# Project.net
KiCad netlist of a schematic drawn in EasyEDA Pro
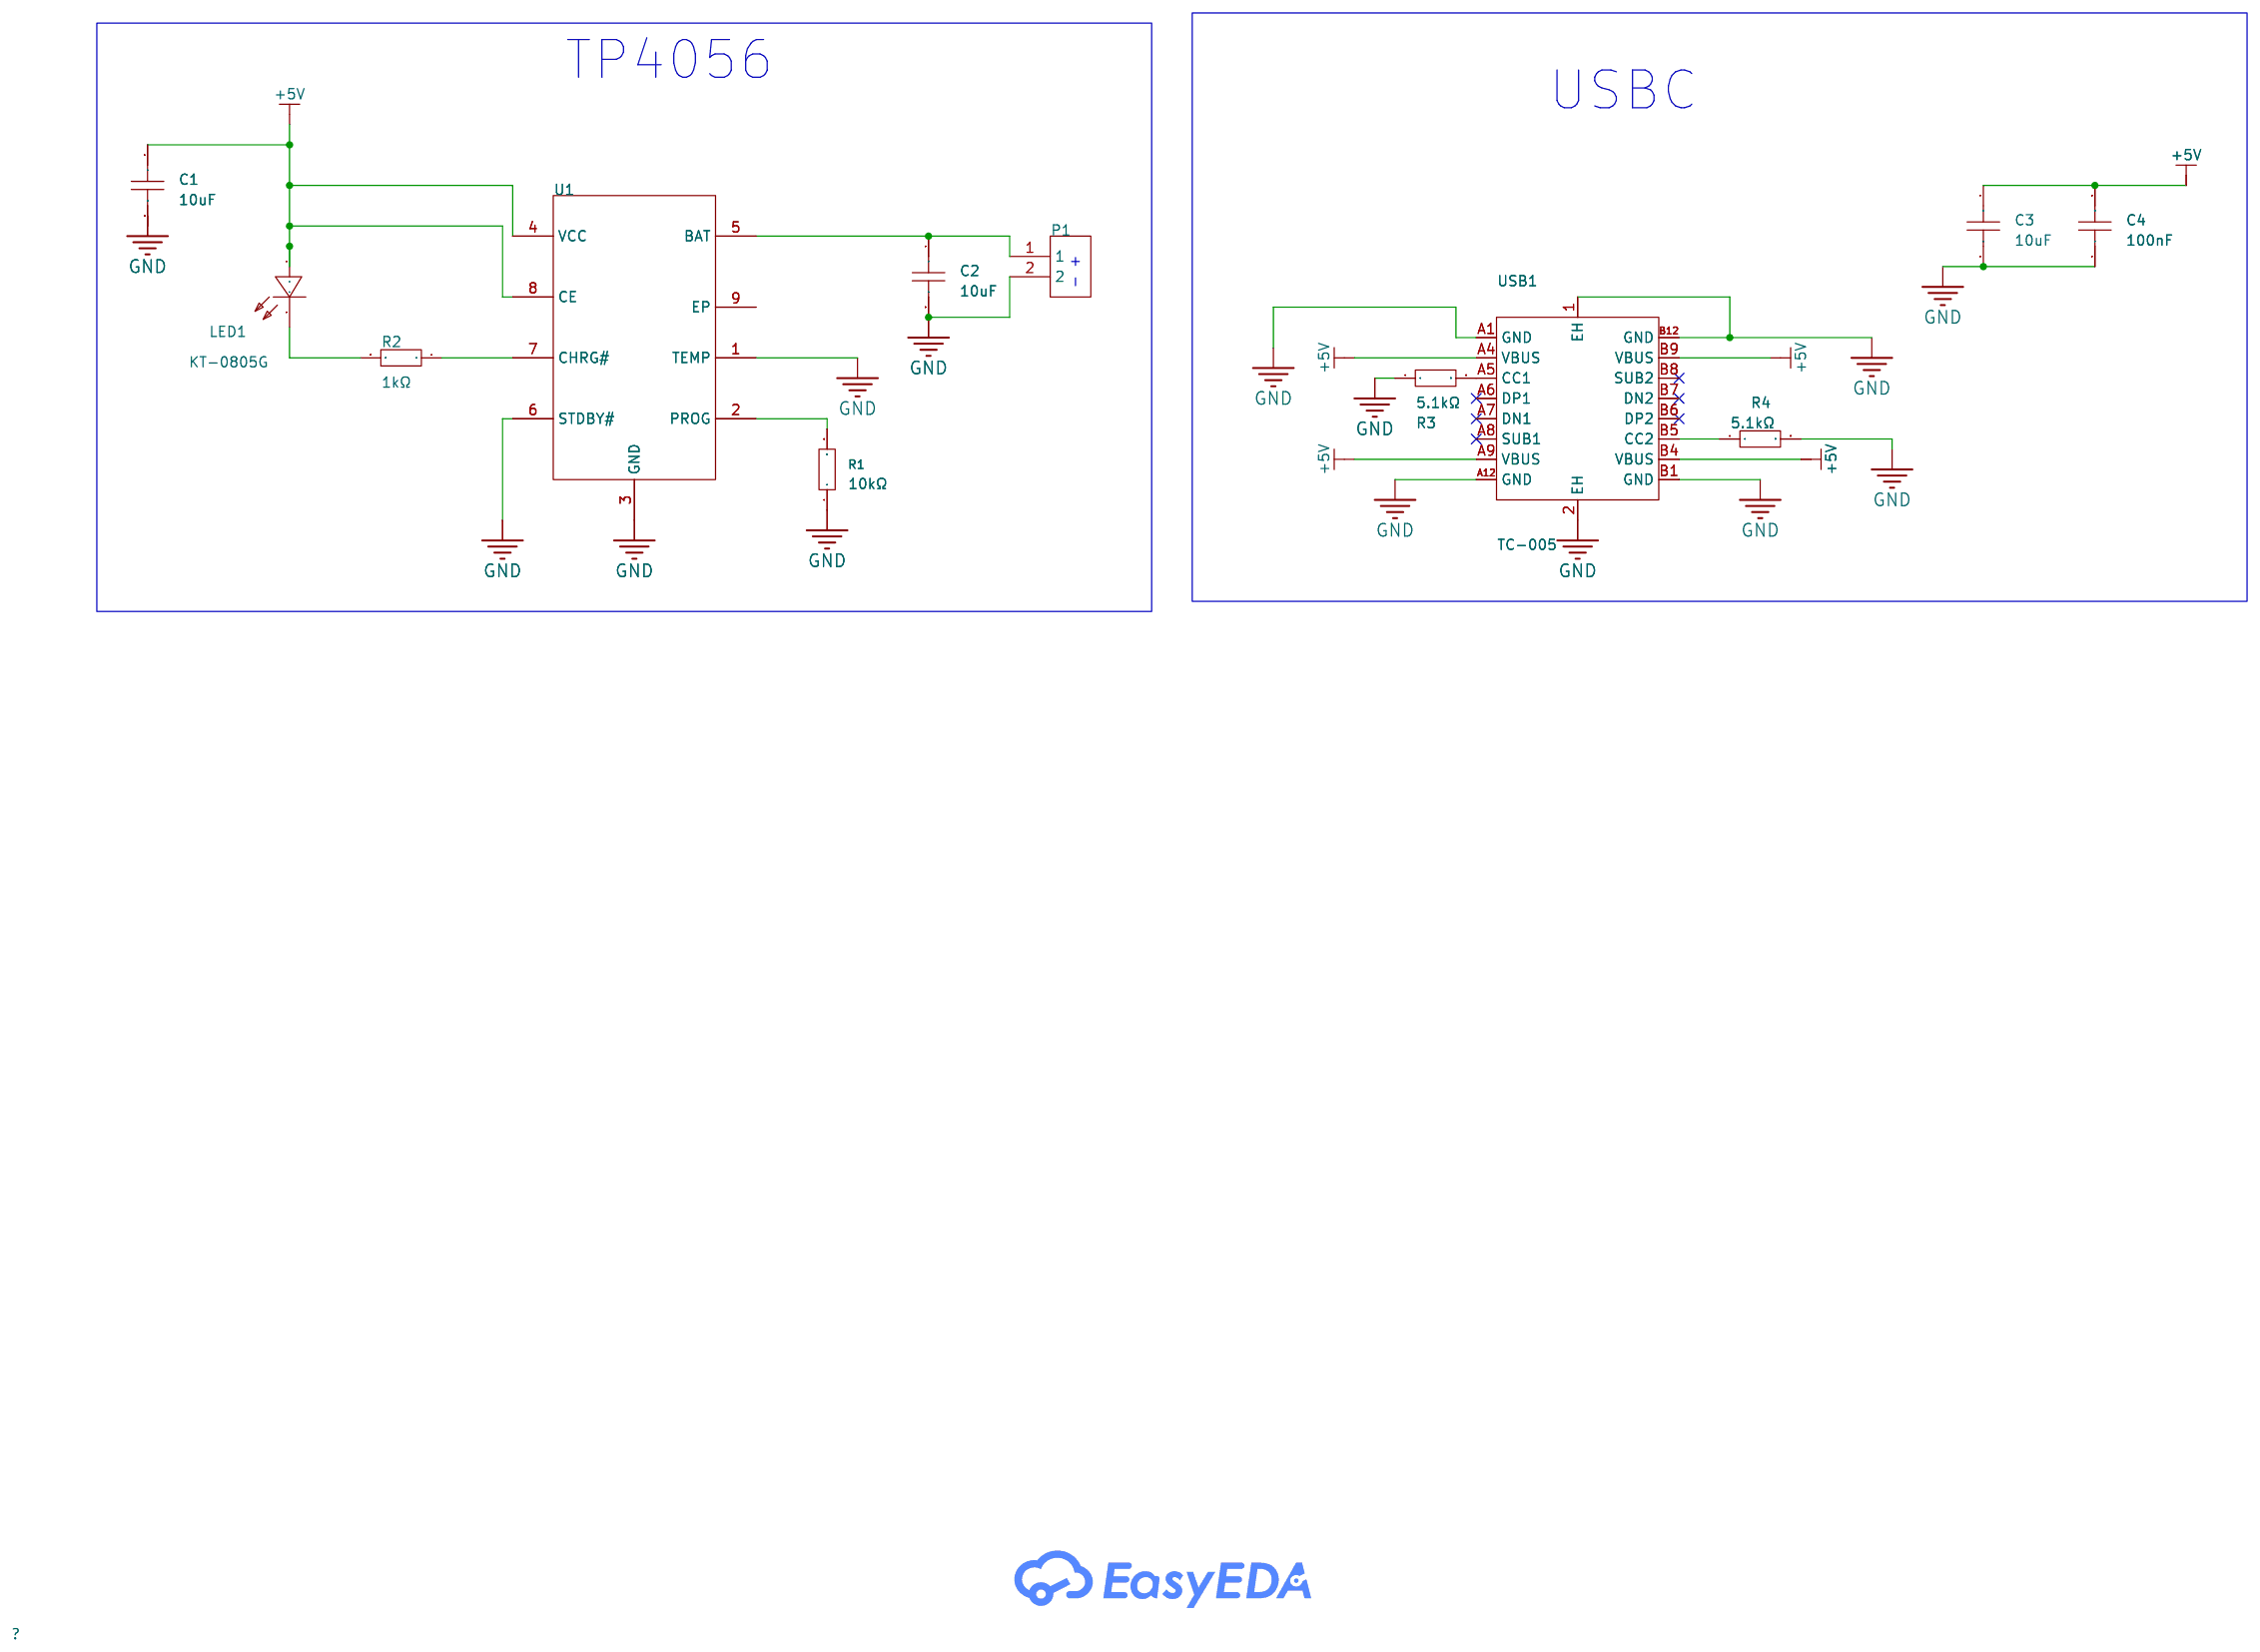
[diagram p0: schematic sheet]

(export (version "E")
  (design (tool "Eeschema 10.0.6"))
  (components
    (comp (ref "C1")
      (value "10uF")
      (footprint "easyedapro:C0805")
      (description "Capacitance:10uF Tolerance:±10% Tolerance:±10% Voltage Rating:25V Temperature Coefficient:X5R")
      (fields
        (field (name "Manufacturer Part") "CL21A106KAYNNNE")
        (field (name "Manufacturer") "SAMSUNG(三星)")
      )
      (libsource (lib "easyedapro") (part "CL21A106KAYNNNE"))
    )
    (comp (ref "C2")
      (value "10uF")
      (footprint "easyedapro:C0805")
      (description "Capacitance:10uF Tolerance:±10% Tolerance:±10% Voltage Rating:25V Temperature Coefficient:X5R")
      (fields
        (field (name "Manufacturer Part") "CL21A106KAYNNNE")
        (field (name "Manufacturer") "SAMSUNG(三星)")
      )
      (libsource (lib "easyedapro") (part "CL21A106KAYNNNE"))
    )
    (comp (ref "C3")
      (value "10uF")
      (footprint "easyedapro:C0805")
      (description "Capacitance:10uF Tolerance:±10% Tolerance:±10% Voltage Rating:25V Temperature Coefficient:X5R")
      (fields
        (field (name "Manufacturer Part") "CL21A106KAYNNNE")
        (field (name "Manufacturer") "SAMSUNG(三星)")
      )
      (libsource (lib "easyedapro") (part "CL21A106KAYNNNE"))
    )
    (comp (ref "C4")
      (value "100nF")
      (footprint "easyedapro:C0402")
      (description "Capacitance:100nF Tolerance:±10% Tolerance:±10% Voltage Rating:16V Temperature Coefficient:X7R")
      (fields
        (field (name "Manufacturer Part") "CL05B104KO5NNNC")
        (field (name "Manufacturer") "SAMSUNG(三星)")
      )
      (libsource (lib "easyedapro") (part "CL05B104KO5NNNC"))
    )
    (comp (ref "LED1")
      (value "KT-0805G")
      (footprint "easyedapro:LED0805-R-RD")
      (fields (field (name "Manufacturer") "KENTO"))
      (libsource (lib "easyedapro") (part "0805G (Green)"))
    )
    (comp (ref "P1")
      (value "WJ301V-5.0-02P-12-00A")
      (footprint "easyedapro:CONN-TH_2P-P5.00_WJ301V-5.00-2P")
      (fields (field (name "Manufacturer") "KANGNEX(康奈克斯电气)"))
      (libsource (lib "easyedapro") (part "WJ301V-5.0-2P"))
    )
    (comp (ref "R1")
      (value "10kΩ")
      (footprint "easyedapro:R1206")
      (fields
        (field (name "Manufacturer Part") "1206W4F1002T5E")
        (field (name "Manufacturer") "UNI-ROYAL(厚声)")
      )
      (libsource (lib "easyedapro") (part "1206W4F1002T5E"))
    )
    (comp (ref "R2")
      (value "1kΩ")
      (footprint "easyedapro:R0402")
      (fields
        (field (name "Manufacturer Part") "0402WGF1001TCE")
        (field (name "Manufacturer") "UNI-ROYAL(厚声)")
      )
      (libsource (lib "easyedapro") (part "0402WGF1001TCE"))
    )
    (comp (ref "R3")
      (value "5.1kΩ")
      (footprint "easyedapro:R0603")
      (fields
        (field (name "Manufacturer Part") "0603WAF5101T5E")
        (field (name "Manufacturer") "UNI-ROYAL(厚声)")
      )
      (libsource (lib "easyedapro") (part "0603WAF5101T5E"))
    )
    (comp (ref "R4")
      (value "5.1kΩ")
      (footprint "easyedapro:R0603")
      (fields
        (field (name "Manufacturer Part") "0603WAF5101T5E")
        (field (name "Manufacturer") "UNI-ROYAL(厚声)")
      )
      (libsource (lib "easyedapro") (part "0603WAF5101T5E"))
    )
    (comp (ref "U1")
      (value "TP4056-42-ESOP8")
      (footprint "easyedapro:ESOP-8_L4.9-W3.9-P1.27-LS6.0-BL-EP")
      (fields (field (name "Manufacturer") "TOPPOWER(南京拓微)"))
      (libsource (lib "easyedapro") (part "TP4056"))
    )
    (comp (ref "USB1")
      (value "TC-005")
      (footprint "easyedapro:USB-C-SMD_TC-005")
      (fields (field (name "Manufacturer") "HANBO(汉博)"))
      (libsource (lib "easyedapro") (part "TC-005_C6332285"))
    )
  )
  (nets
    (net (code "1") (name "+5V") (class "Default")
      (node (ref "C1") (pin "1") (pinfunction "1_1") (pintype "unspecified"))
      (node (ref "C3") (pin "1") (pinfunction "1_1") (pintype "unspecified"))
      (node (ref "C4") (pin "2") (pinfunction "2_2") (pintype "unspecified"))
      (node (ref "LED1") (pin "1") (pinfunction "A_1") (pintype "unspecified"))
      (node (ref "U1") (pin "4") (pinfunction "VCC_4") (pintype "unspecified"))
      (node (ref "U1") (pin "8") (pinfunction "CE_8") (pintype "unspecified"))
      (node (ref "USB1") (pin "A4") (pinfunction "VBUS_A4") (pintype "unspecified"))
      (node (ref "USB1") (pin "A9") (pinfunction "VBUS_A9") (pintype "unspecified"))
      (node (ref "USB1") (pin "B4") (pinfunction "VBUS_B4") (pintype "unspecified"))
      (node (ref "USB1") (pin "B9") (pinfunction "VBUS_B9") (pintype "unspecified"))
    )
    (net (code "2") (name "GND") (class "Default")
      (node (ref "C1") (pin "2") (pinfunction "2_2") (pintype "unspecified"))
      (node (ref "C2") (pin "2") (pinfunction "2_2") (pintype "unspecified"))
      (node (ref "C3") (pin "2") (pinfunction "2_2") (pintype "unspecified"))
      (node (ref "C4") (pin "1") (pinfunction "1_1") (pintype "unspecified"))
      (node (ref "P1") (pin "2") (pinfunction "2_2") (pintype "unspecified"))
      (node (ref "R1") (pin "1") (pinfunction "1_1") (pintype "input"))
      (node (ref "R3") (pin "1") (pinfunction "1_1") (pintype "input"))
      (node (ref "R4") (pin "2") (pinfunction "2_2") (pintype "input"))
      (node (ref "U1") (pin "1") (pinfunction "TEMP_1") (pintype "unspecified"))
      (node (ref "U1") (pin "3") (pinfunction "GND_3") (pintype "unspecified"))
      (node (ref "U1") (pin "6") (pinfunction "STDBY#_6") (pintype "unspecified"))
      (node (ref "USB1") (pin "1") (pinfunction "EH_1") (pintype "unspecified"))
      (node (ref "USB1") (pin "2") (pinfunction "EH_2") (pintype "unspecified"))
      (node (ref "USB1") (pin "A1") (pinfunction "GND_A1") (pintype "unspecified"))
      (node (ref "USB1") (pin "A12") (pinfunction "GND_A12") (pintype "unspecified"))
      (node (ref "USB1") (pin "B1") (pinfunction "GND_B1") (pintype "unspecified"))
      (node (ref "USB1") (pin "B12") (pinfunction "GND_B12") (pintype "unspecified"))
    )
    (net (code "3") (name "Net-(LED1-K)") (class "Default")
      (node (ref "LED1") (pin "2") (pinfunction "K_2") (pintype "unspecified"))
      (node (ref "R2") (pin "2") (pinfunction "2_2") (pintype "input"))
    )
    (net (code "4") (name "Net-(U1-BAT)") (class "Default")
      (node (ref "C2") (pin "1") (pinfunction "1_1") (pintype "unspecified"))
      (node (ref "P1") (pin "1") (pinfunction "1_1") (pintype "unspecified"))
      (node (ref "U1") (pin "5") (pinfunction "BAT_5") (pintype "unspecified"))
    )
    (net (code "5") (name "Net-(U1-CHRG#)") (class "Default")
      (node (ref "R2") (pin "1") (pinfunction "1_1") (pintype "input"))
      (node (ref "U1") (pin "7") (pinfunction "CHRG#_7") (pintype "unspecified"))
    )
    (net (code "6") (name "Net-(U1-PROG)") (class "Default")
      (node (ref "R1") (pin "2") (pinfunction "2_2") (pintype "input"))
      (node (ref "U1") (pin "2") (pinfunction "PROG_2") (pintype "unspecified"))
    )
    (net (code "7") (name "Net-(USB1-CC1)") (class "Default")
      (node (ref "R3") (pin "2") (pinfunction "2_2") (pintype "input"))
      (node (ref "USB1") (pin "A5") (pinfunction "CC1_A5") (pintype "unspecified"))
    )
    (net (code "8") (name "Net-(USB1-CC2)") (class "Default")
      (node (ref "R4") (pin "1") (pinfunction "1_1") (pintype "input"))
      (node (ref "USB1") (pin "B5") (pinfunction "CC2_B5") (pintype "unspecified"))
    )
    (net (code "9") (name "unconnected-(U1-EP-Pad9)") (class "Default")
      (node (ref "U1") (pin "9") (pinfunction "EP_9") (pintype "unspecified"))
    )
    (net (code "10") (name "unconnected-(USB1-DN1-PadA7)") (class "Default")
      (node (ref "USB1") (pin "A7") (pinfunction "DN1_A7") (pintype "unspecified+no_connect"))
    )
    (net (code "11") (name "unconnected-(USB1-DN2-PadB7)") (class "Default")
      (node (ref "USB1") (pin "B7") (pinfunction "DN2_B7") (pintype "unspecified+no_connect"))
    )
    (net (code "12") (name "unconnected-(USB1-DP1-PadA6)") (class "Default")
      (node (ref "USB1") (pin "A6") (pinfunction "DP1_A6") (pintype "unspecified+no_connect"))
    )
    (net (code "13") (name "unconnected-(USB1-DP2-PadB6)") (class "Default")
      (node (ref "USB1") (pin "B6") (pinfunction "DP2_B6") (pintype "unspecified+no_connect"))
    )
    (net (code "14") (name "unconnected-(USB1-SUB1-PadA8)") (class "Default")
      (node (ref "USB1") (pin "A8") (pinfunction "SUB1_A8") (pintype "unspecified+no_connect"))
    )
    (net (code "15") (name "unconnected-(USB1-SUB2-PadB8)") (class "Default")
      (node (ref "USB1") (pin "B8") (pinfunction "SUB2_B8") (pintype "unspecified+no_connect"))
    )
  )
)
